# dualHbridge-v4.net
KiCad netlist of a schematic drawn in EAGLE
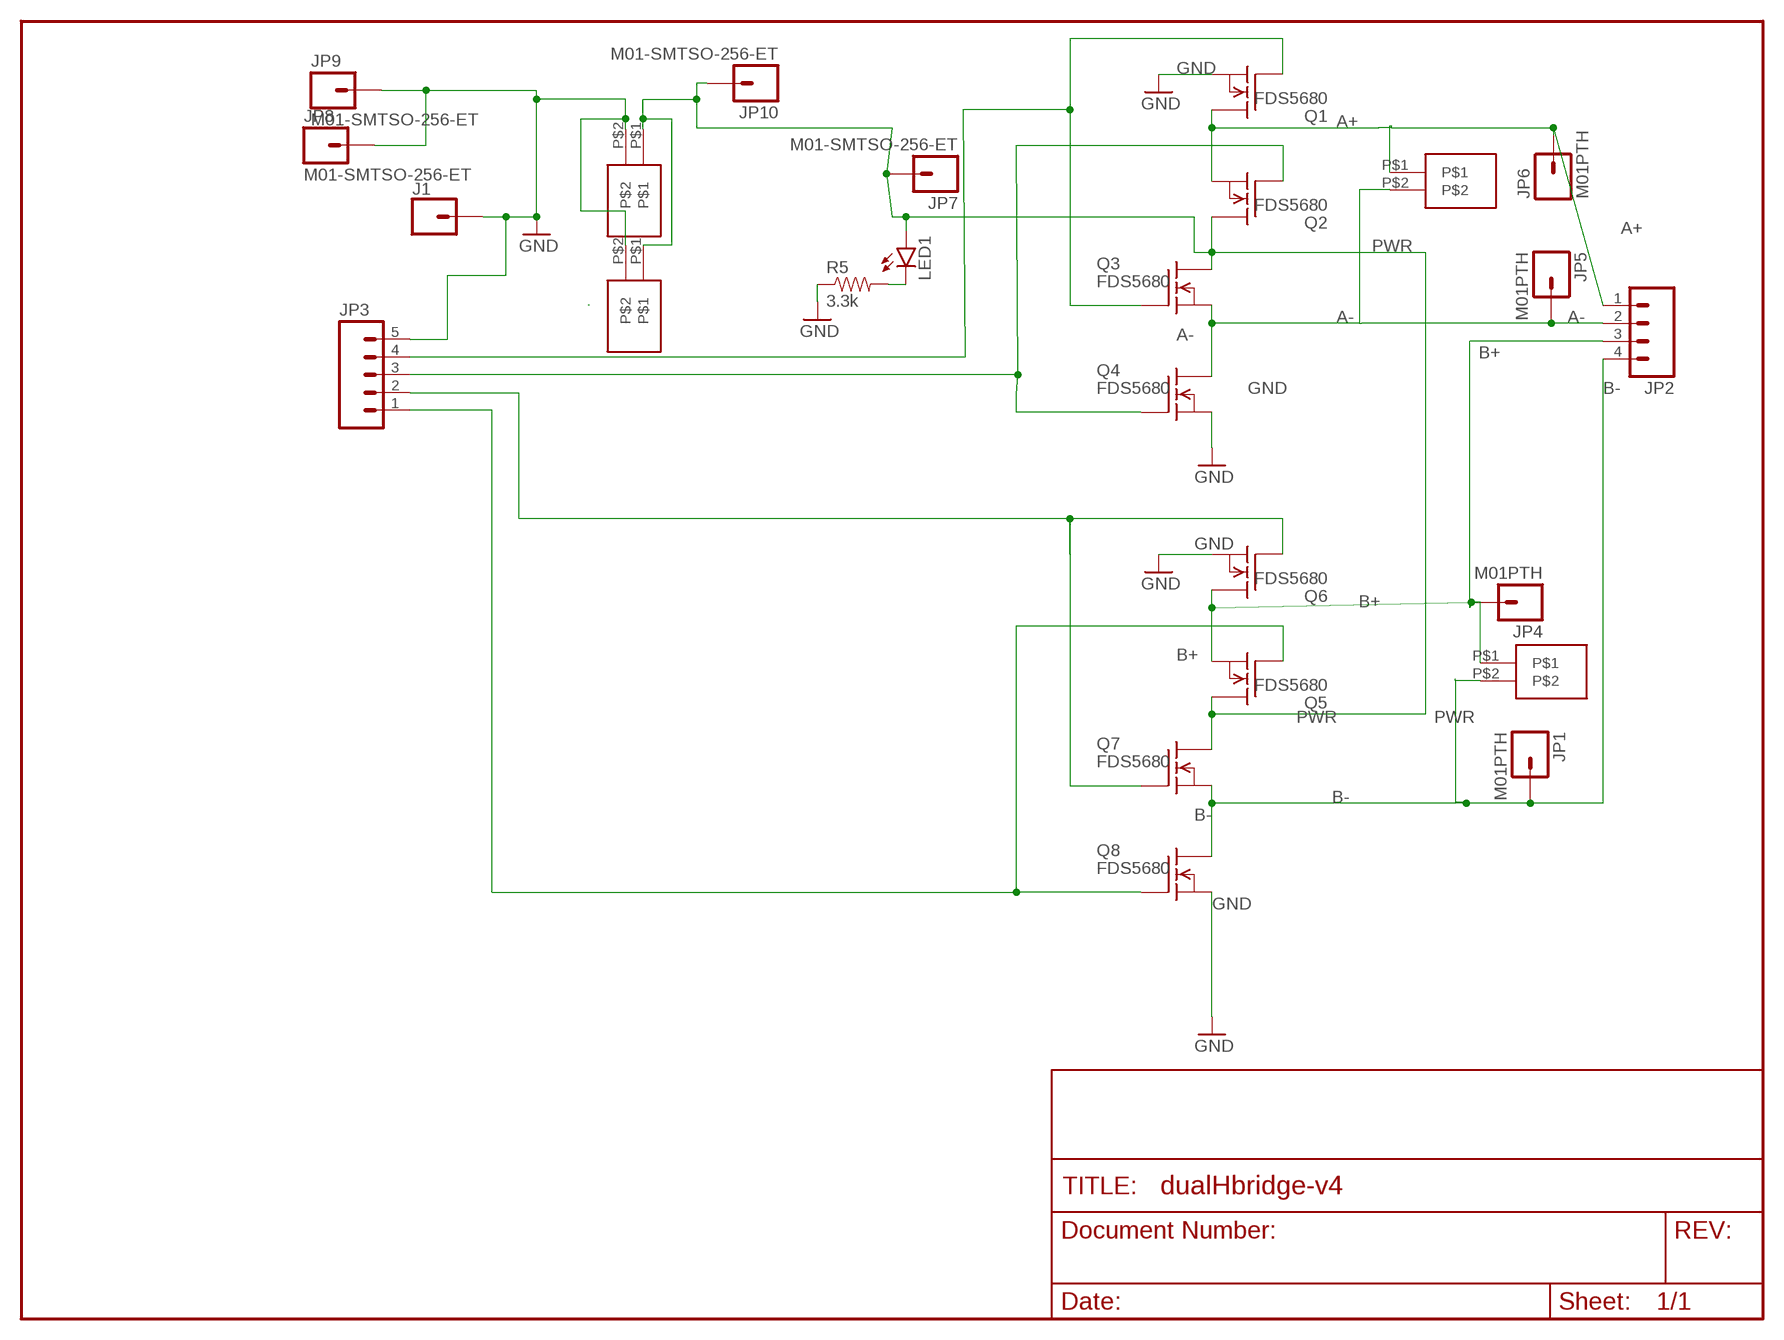
[diagram p0: schematic, sheet 1]

(export (version "E")
  (design (tool "Eeschema 10.0.6"))
  (components
    (comp (ref "J1")
      (value "CONN_01")
      (footprint "eagle-import:1X01")
      (libsource (lib "eagle-import") (part "CONN_01"))
    )
    (comp (ref "JP1")
      (value "M01PTH")
      (footprint "eagle-import:1X01@1")
      (libsource (lib "eagle-import") (part "M01PTH"))
    )
    (comp (ref "JP2")
      (value "M04LONGPADS")
      (footprint "eagle-import:1X04_LONGPADS")
      (libsource (lib "eagle-import") (part "M04LONGPADS"))
    )
    (comp (ref "JP3")
      (value "M05PTH")
      (footprint "eagle-import:1X05")
      (libsource (lib "eagle-import") (part "M05PTH"))
    )
    (comp (ref "JP4")
      (value "M01PTH")
      (footprint "eagle-import:1X01@1")
      (libsource (lib "eagle-import") (part "M01PTH"))
    )
    (comp (ref "JP5")
      (value "M01PTH")
      (footprint "eagle-import:1X01@1")
      (libsource (lib "eagle-import") (part "M01PTH"))
    )
    (comp (ref "JP6")
      (value "M01PTH")
      (footprint "eagle-import:1X01@1")
      (libsource (lib "eagle-import") (part "M01PTH"))
    )
    (comp (ref "JP7")
      (value "M01-SMTSO-256-ET")
      (footprint "eagle-import:SMTSO-256-ET")
      (libsource (lib "eagle-import") (part "M01-SMTSO-256-ET"))
    )
    (comp (ref "JP8")
      (value "M01-SMTSO-256-ET")
      (footprint "eagle-import:SMTSO-256-ET")
      (libsource (lib "eagle-import") (part "M01-SMTSO-256-ET"))
    )
    (comp (ref "JP9")
      (value "M01-SMTSO-256-ET")
      (footprint "eagle-import:SMTSO-256-ET")
      (libsource (lib "eagle-import") (part "M01-SMTSO-256-ET"))
    )
    (comp (ref "JP10")
      (value "M01-SMTSO-256-ET")
      (footprint "eagle-import:SMTSO-256-ET")
      (libsource (lib "eagle-import") (part "M01-SMTSO-256-ET"))
    )
    (comp (ref "LED1")
      (value "LED5MM")
      (footprint "eagle-import:LED5MM")
      (libsource (lib "eagle-import") (part "LED5MM"))
    )
    (comp (ref "Q1")
      (value "FDS5680")
      (footprint "eagle-import:SO-8")
      (libsource (lib "eagle-import") (part "FDS5680"))
    )
    (comp (ref "Q2")
      (value "FDS5680")
      (footprint "eagle-import:SO-8")
      (libsource (lib "eagle-import") (part "FDS5680"))
    )
    (comp (ref "Q3")
      (value "FDS5680")
      (footprint "eagle-import:SO-8")
      (libsource (lib "eagle-import") (part "FDS5680"))
    )
    (comp (ref "Q4")
      (value "FDS5680")
      (footprint "eagle-import:SO-8")
      (libsource (lib "eagle-import") (part "FDS5680"))
    )
    (comp (ref "Q5")
      (value "FDS5680")
      (footprint "eagle-import:SO-8")
      (libsource (lib "eagle-import") (part "FDS5680"))
    )
    (comp (ref "Q6")
      (value "FDS5680")
      (footprint "eagle-import:SO-8")
      (libsource (lib "eagle-import") (part "FDS5680"))
    )
    (comp (ref "Q7")
      (value "FDS5680")
      (footprint "eagle-import:SO-8")
      (libsource (lib "eagle-import") (part "FDS5680"))
    )
    (comp (ref "Q8")
      (value "FDS5680")
      (footprint "eagle-import:SO-8")
      (libsource (lib "eagle-import") (part "FDS5680"))
    )
    (comp (ref "R5")
      (value "3.3k")
      (footprint "eagle-import:0603-RES")
      (libsource (lib "eagle-import") (part "RESISTOR0603-RES"))
    )
    (comp (ref "U$1")
      (value "SPRING-TERMINAL")
      (footprint "eagle-import:SPRING-TERMINAL")
      (libsource (lib "eagle-import") (part "SPRING-TERMINAL"))
    )
    (comp (ref "U$2")
      (value "SPRING-TERMINAL")
      (footprint "eagle-import:SPRING-TERMINAL")
      (libsource (lib "eagle-import") (part "SPRING-TERMINAL"))
    )
    (comp (ref "U$3")
      (value "SPRING-TERMINAL")
      (footprint "eagle-import:SPRING-TERMINAL")
      (libsource (lib "eagle-import") (part "SPRING-TERMINAL"))
    )
    (comp (ref "U$4")
      (value "SPRING-TERMINAL")
      (footprint "eagle-import:SPRING-TERMINAL")
      (libsource (lib "eagle-import") (part "SPRING-TERMINAL"))
    )
  )
  (nets
    (net (code "1") (name "/A+") (class "Default")
      (node (ref "JP2") (pin "1") (pinfunction "1_1") (pintype "passive"))
      (node (ref "JP6") (pin "1") (pinfunction "1_1") (pintype "passive"))
      (node (ref "Q1") (pin "5") (pinfunction "D_5") (pintype "passive"))
      (node (ref "Q1") (pin "6") (pinfunction "D_6") (pintype "passive"))
      (node (ref "Q1") (pin "7") (pinfunction "D_7") (pintype "passive"))
      (node (ref "Q1") (pin "8") (pinfunction "D_8") (pintype "passive"))
      (node (ref "Q2") (pin "1") (pinfunction "S_1") (pintype "passive"))
      (node (ref "Q2") (pin "2") (pinfunction "S_2") (pintype "passive"))
      (node (ref "Q2") (pin "3") (pinfunction "S_3") (pintype "passive"))
      (node (ref "U$1") (pin "P$1") (pinfunction "P$1_P$1") (pintype "bidirectional"))
    )
    (net (code "2") (name "/A-") (class "Default")
      (node (ref "JP2") (pin "2") (pinfunction "2_2") (pintype "passive"))
      (node (ref "JP5") (pin "1") (pinfunction "1_1") (pintype "passive"))
      (node (ref "Q3") (pin "1") (pinfunction "S_1") (pintype "passive"))
      (node (ref "Q3") (pin "2") (pinfunction "S_2") (pintype "passive"))
      (node (ref "Q3") (pin "3") (pinfunction "S_3") (pintype "passive"))
      (node (ref "Q4") (pin "5") (pinfunction "D_5") (pintype "passive"))
      (node (ref "Q4") (pin "6") (pinfunction "D_6") (pintype "passive"))
      (node (ref "Q4") (pin "7") (pinfunction "D_7") (pintype "passive"))
      (node (ref "Q4") (pin "8") (pinfunction "D_8") (pintype "passive"))
      (node (ref "U$1") (pin "P$2") (pinfunction "P$2_P$2") (pintype "bidirectional"))
    )
    (net (code "3") (name "/B+") (class "Default")
      (node (ref "JP2") (pin "3") (pinfunction "3_3") (pintype "passive"))
      (node (ref "JP4") (pin "1") (pinfunction "1_1") (pintype "passive"))
      (node (ref "Q5") (pin "1") (pinfunction "S_1") (pintype "passive"))
      (node (ref "Q5") (pin "2") (pinfunction "S_2") (pintype "passive"))
      (node (ref "Q5") (pin "3") (pinfunction "S_3") (pintype "passive"))
      (node (ref "Q6") (pin "5") (pinfunction "D_5") (pintype "passive"))
      (node (ref "Q6") (pin "6") (pinfunction "D_6") (pintype "passive"))
      (node (ref "Q6") (pin "7") (pinfunction "D_7") (pintype "passive"))
      (node (ref "Q6") (pin "8") (pinfunction "D_8") (pintype "passive"))
      (node (ref "U$3") (pin "P$1") (pinfunction "P$1_P$1") (pintype "bidirectional"))
    )
    (net (code "4") (name "/B-") (class "Default")
      (node (ref "JP1") (pin "1") (pinfunction "1_1") (pintype "passive"))
      (node (ref "JP2") (pin "4") (pinfunction "4_4") (pintype "passive"))
      (node (ref "Q7") (pin "1") (pinfunction "S_1") (pintype "passive"))
      (node (ref "Q7") (pin "2") (pinfunction "S_2") (pintype "passive"))
      (node (ref "Q7") (pin "3") (pinfunction "S_3") (pintype "passive"))
      (node (ref "Q8") (pin "5") (pinfunction "D_5") (pintype "passive"))
      (node (ref "Q8") (pin "6") (pinfunction "D_6") (pintype "passive"))
      (node (ref "Q8") (pin "7") (pinfunction "D_7") (pintype "passive"))
      (node (ref "Q8") (pin "8") (pinfunction "D_8") (pintype "passive"))
      (node (ref "U$3") (pin "P$2") (pinfunction "P$2_P$2") (pintype "bidirectional"))
    )
    (net (code "5") (name "/PWR") (class "Default")
      (node (ref "JP10") (pin "P$1") (pinfunction "1_P$1") (pintype "passive"))
      (node (ref "JP7") (pin "P$1") (pinfunction "1_P$1") (pintype "passive"))
      (node (ref "LED1") (pin "A") (pinfunction "A_A") (pintype "passive"))
      (node (ref "Q2") (pin "5") (pinfunction "D_5") (pintype "passive"))
      (node (ref "Q2") (pin "6") (pinfunction "D_6") (pintype "passive"))
      (node (ref "Q2") (pin "7") (pinfunction "D_7") (pintype "passive"))
      (node (ref "Q2") (pin "8") (pinfunction "D_8") (pintype "passive"))
      (node (ref "Q3") (pin "5") (pinfunction "D_5") (pintype "passive"))
      (node (ref "Q3") (pin "6") (pinfunction "D_6") (pintype "passive"))
      (node (ref "Q3") (pin "7") (pinfunction "D_7") (pintype "passive"))
      (node (ref "Q3") (pin "8") (pinfunction "D_8") (pintype "passive"))
      (node (ref "Q5") (pin "5") (pinfunction "D_5") (pintype "passive"))
      (node (ref "Q5") (pin "6") (pinfunction "D_6") (pintype "passive"))
      (node (ref "Q5") (pin "7") (pinfunction "D_7") (pintype "passive"))
      (node (ref "Q5") (pin "8") (pinfunction "D_8") (pintype "passive"))
      (node (ref "Q7") (pin "5") (pinfunction "D_5") (pintype "passive"))
      (node (ref "Q7") (pin "6") (pinfunction "D_6") (pintype "passive"))
      (node (ref "Q7") (pin "7") (pinfunction "D_7") (pintype "passive"))
      (node (ref "Q7") (pin "8") (pinfunction "D_8") (pintype "passive"))
      (node (ref "U$2") (pin "P$1") (pinfunction "P$1_P$1") (pintype "bidirectional"))
      (node (ref "U$4") (pin "P$1") (pinfunction "P$1_P$1") (pintype "bidirectional"))
    )
    (net (code "6") (name "GND") (class "Default")
      (node (ref "J1") (pin "1") (pinfunction "1_1") (pintype "passive"))
      (node (ref "JP3") (pin "5") (pinfunction "5_5") (pintype "passive"))
      (node (ref "JP8") (pin "P$1") (pinfunction "1_P$1") (pintype "passive"))
      (node (ref "JP9") (pin "P$1") (pinfunction "1_P$1") (pintype "passive"))
      (node (ref "Q1") (pin "1") (pinfunction "S_1") (pintype "passive"))
      (node (ref "Q1") (pin "2") (pinfunction "S_2") (pintype "passive"))
      (node (ref "Q1") (pin "3") (pinfunction "S_3") (pintype "passive"))
      (node (ref "Q4") (pin "1") (pinfunction "S_1") (pintype "passive"))
      (node (ref "Q4") (pin "2") (pinfunction "S_2") (pintype "passive"))
      (node (ref "Q4") (pin "3") (pinfunction "S_3") (pintype "passive"))
      (node (ref "Q6") (pin "1") (pinfunction "S_1") (pintype "passive"))
      (node (ref "Q6") (pin "2") (pinfunction "S_2") (pintype "passive"))
      (node (ref "Q6") (pin "3") (pinfunction "S_3") (pintype "passive"))
      (node (ref "Q8") (pin "1") (pinfunction "S_1") (pintype "passive"))
      (node (ref "Q8") (pin "2") (pinfunction "S_2") (pintype "passive"))
      (node (ref "Q8") (pin "3") (pinfunction "S_3") (pintype "passive"))
      (node (ref "R5") (pin "1") (pinfunction "1_1") (pintype "passive"))
      (node (ref "U$2") (pin "P$2") (pinfunction "P$2_P$2") (pintype "bidirectional"))
      (node (ref "U$4") (pin "P$2") (pinfunction "P$2_P$2") (pintype "bidirectional"))
    )
    (net (code "7") (name "Net-(LED1-C)") (class "Default")
      (node (ref "LED1") (pin "K") (pinfunction "C_K") (pintype "passive"))
      (node (ref "R5") (pin "2") (pinfunction "2_2") (pintype "passive"))
    )
    (net (code "8") (name "Net-(Q1-G)") (class "Default")
      (node (ref "JP3") (pin "4") (pinfunction "4_4") (pintype "passive"))
      (node (ref "Q1") (pin "4") (pinfunction "G_4") (pintype "passive"))
      (node (ref "Q3") (pin "4") (pinfunction "G_4") (pintype "passive"))
    )
    (net (code "9") (name "Net-(Q2-G)") (class "Default")
      (node (ref "JP3") (pin "3") (pinfunction "3_3") (pintype "passive"))
      (node (ref "Q2") (pin "4") (pinfunction "G_4") (pintype "passive"))
      (node (ref "Q4") (pin "4") (pinfunction "G_4") (pintype "passive"))
    )
    (net (code "10") (name "Net-(Q5-G)") (class "Default")
      (node (ref "JP3") (pin "1") (pinfunction "1_1") (pintype "passive"))
      (node (ref "Q5") (pin "4") (pinfunction "G_4") (pintype "passive"))
      (node (ref "Q8") (pin "4") (pinfunction "G_4") (pintype "passive"))
    )
    (net (code "11") (name "Net-(Q6-G)") (class "Default")
      (node (ref "JP3") (pin "2") (pinfunction "2_2") (pintype "passive"))
      (node (ref "Q6") (pin "4") (pinfunction "G_4") (pintype "passive"))
      (node (ref "Q7") (pin "4") (pinfunction "G_4") (pintype "passive"))
    )
  )
)
